# LORA.net
KiCad netlist of a schematic drawn in Altium Designer
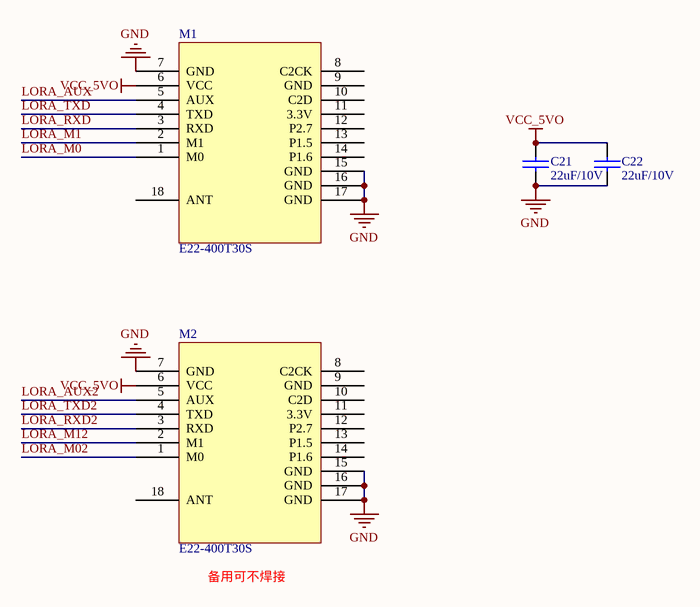
[diagram p0: LORA.SchDoc]

(export (version "E")
  (design (tool "Eeschema 10.0.6"))
  (components
    (comp (ref "C21")
      (value "22uF/10V")
      (footprint "1206C")
      (description "Capacitor")
      (libsource (lib "ZWLIntegrated_Library") (part "CAP"))
    )
    (comp (ref "C22")
      (value "22uF/10V")
      (footprint "1206C")
      (description "Capacitor")
      (libsource (lib "ZWLIntegrated_Library") (part "CAP"))
    )
    (comp (ref "M1")
      (value "E22-400T30S")
      (footprint "E22-400T30S")
      (libsource (lib "stm32") (part "E22-400T30S"))
    )
    (comp (ref "M2")
      (value "E22-400T30S")
      (footprint "E22-400T30S")
      (libsource (lib "stm32") (part "E22-400T30S"))
    )
  )
  (nets
    (net (code "1") (name "/LORA_AUX") (class "Default")
      (node (ref "M1") (pin "5") (pinfunction "AUX_5") (pintype "passive"))
    )
    (net (code "2") (name "/LORA_AUX2") (class "Default")
      (node (ref "M2") (pin "5") (pinfunction "AUX_5") (pintype "passive"))
    )
    (net (code "3") (name "/LORA_M0") (class "Default")
      (node (ref "M1") (pin "1") (pinfunction "M0_1") (pintype "passive"))
    )
    (net (code "4") (name "/LORA_M1") (class "Default")
      (node (ref "M1") (pin "2") (pinfunction "M1_2") (pintype "passive"))
    )
    (net (code "5") (name "/LORA_M02") (class "Default")
      (node (ref "M2") (pin "1") (pinfunction "M0_1") (pintype "passive"))
    )
    (net (code "6") (name "/LORA_M12") (class "Default")
      (node (ref "M2") (pin "2") (pinfunction "M1_2") (pintype "passive"))
    )
    (net (code "7") (name "/LORA_RXD") (class "Default")
      (node (ref "M1") (pin "3") (pinfunction "RXD_3") (pintype "passive"))
    )
    (net (code "8") (name "/LORA_RXD2") (class "Default")
      (node (ref "M2") (pin "3") (pinfunction "RXD_3") (pintype "passive"))
    )
    (net (code "9") (name "/LORA_TXD") (class "Default")
      (node (ref "M1") (pin "4") (pinfunction "TXD_4") (pintype "passive"))
    )
    (net (code "10") (name "/LORA_TXD2") (class "Default")
      (node (ref "M2") (pin "4") (pinfunction "TXD_4") (pintype "passive"))
    )
    (net (code "11") (name "GND") (class "Default")
      (node (ref "C21") (pin "2") (pinfunction "2_2") (pintype "passive"))
      (node (ref "C22") (pin "2") (pinfunction "2_2") (pintype "passive"))
      (node (ref "M1") (pin "15") (pinfunction "GND_15") (pintype "passive"))
      (node (ref "M1") (pin "16") (pinfunction "GND_16") (pintype "passive"))
      (node (ref "M1") (pin "17") (pinfunction "GND_17") (pintype "passive"))
      (node (ref "M1") (pin "7") (pinfunction "GND_7") (pintype "passive"))
      (node (ref "M2") (pin "15") (pinfunction "GND_15") (pintype "passive"))
      (node (ref "M2") (pin "16") (pinfunction "GND_16") (pintype "passive"))
      (node (ref "M2") (pin "17") (pinfunction "GND_17") (pintype "passive"))
      (node (ref "M2") (pin "7") (pinfunction "GND_7") (pintype "passive"))
    )
    (net (code "12") (name "VCC_5VO") (class "Default")
      (node (ref "C21") (pin "1") (pinfunction "1_1") (pintype "passive"))
      (node (ref "C22") (pin "1") (pinfunction "1_1") (pintype "passive"))
      (node (ref "M1") (pin "6") (pinfunction "VCC_6") (pintype "passive"))
      (node (ref "M2") (pin "6") (pinfunction "VCC_6") (pintype "passive"))
    )
    (net (code "13") (name "unconnected-(M1-3.3V-Pad11)") (class "Default")
      (node (ref "M1") (pin "11") (pinfunction "3.3V_11") (pintype "passive"))
    )
    (net (code "14") (name "unconnected-(M1-ANT-Pad18)") (class "Default")
      (node (ref "M1") (pin "18") (pinfunction "ANT_18") (pintype "passive"))
    )
    (net (code "15") (name "unconnected-(M1-C2CK-Pad8)") (class "Default")
      (node (ref "M1") (pin "8") (pinfunction "C2CK_8") (pintype "passive"))
    )
    (net (code "16") (name "unconnected-(M1-C2D-Pad10)") (class "Default")
      (node (ref "M1") (pin "10") (pinfunction "C2D_10") (pintype "passive"))
    )
    (net (code "17") (name "unconnected-(M1-GND-Pad9)") (class "Default")
      (node (ref "M1") (pin "9") (pinfunction "GND_9") (pintype "passive"))
    )
    (net (code "18") (name "unconnected-(M1-P1.5-Pad13)") (class "Default")
      (node (ref "M1") (pin "13") (pinfunction "P1.5_13") (pintype "passive"))
    )
    (net (code "19") (name "unconnected-(M1-P1.6-Pad14)") (class "Default")
      (node (ref "M1") (pin "14") (pinfunction "P1.6_14") (pintype "passive"))
    )
    (net (code "20") (name "unconnected-(M1-P2.7-Pad12)") (class "Default")
      (node (ref "M1") (pin "12") (pinfunction "P2.7_12") (pintype "passive"))
    )
    (net (code "21") (name "unconnected-(M2-3.3V-Pad11)") (class "Default")
      (node (ref "M2") (pin "11") (pinfunction "3.3V_11") (pintype "passive"))
    )
    (net (code "22") (name "unconnected-(M2-ANT-Pad18)") (class "Default")
      (node (ref "M2") (pin "18") (pinfunction "ANT_18") (pintype "passive"))
    )
    (net (code "23") (name "unconnected-(M2-C2CK-Pad8)") (class "Default")
      (node (ref "M2") (pin "8") (pinfunction "C2CK_8") (pintype "passive"))
    )
    (net (code "24") (name "unconnected-(M2-C2D-Pad10)") (class "Default")
      (node (ref "M2") (pin "10") (pinfunction "C2D_10") (pintype "passive"))
    )
    (net (code "25") (name "unconnected-(M2-GND-Pad9)") (class "Default")
      (node (ref "M2") (pin "9") (pinfunction "GND_9") (pintype "passive"))
    )
    (net (code "26") (name "unconnected-(M2-P1.5-Pad13)") (class "Default")
      (node (ref "M2") (pin "13") (pinfunction "P1.5_13") (pintype "passive"))
    )
    (net (code "27") (name "unconnected-(M2-P1.6-Pad14)") (class "Default")
      (node (ref "M2") (pin "14") (pinfunction "P1.6_14") (pintype "passive"))
    )
    (net (code "28") (name "unconnected-(M2-P2.7-Pad12)") (class "Default")
      (node (ref "M2") (pin "12") (pinfunction "P2.7_12") (pintype "passive"))
    )
  )
)
